# 01-ESP32-ps2-blueretro.net
KiCad netlist of a schematic drawn in Altium Designer
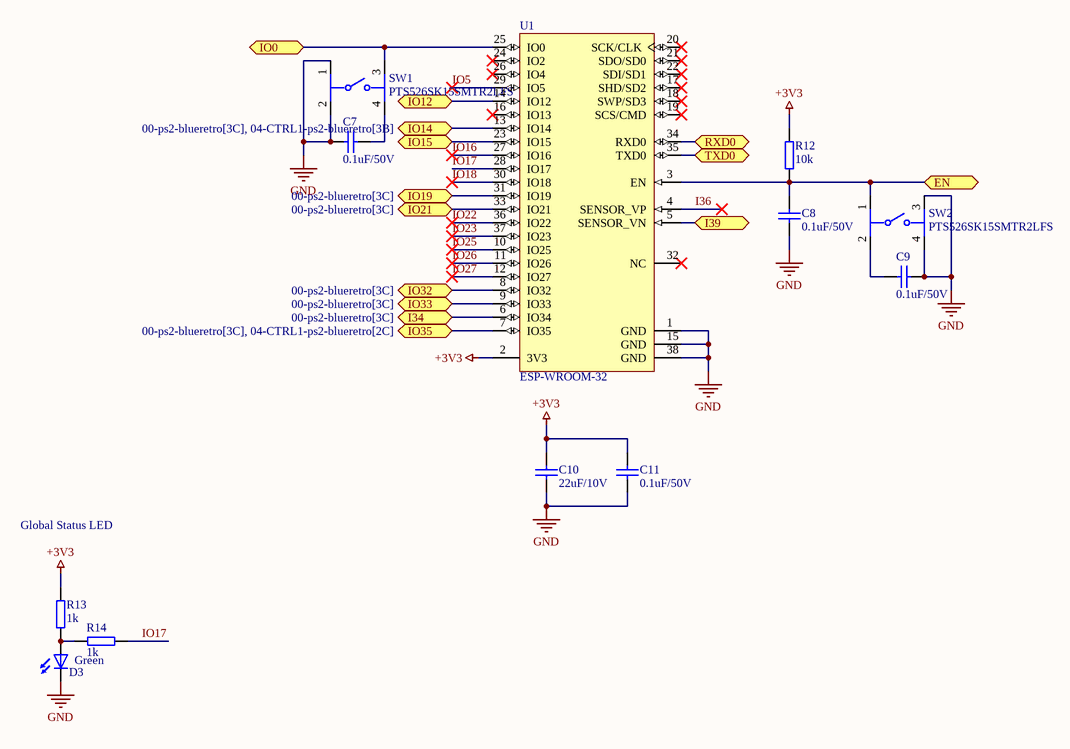
[diagram p0: 01-ESP32-ps2-blueretro.SchDoc]

(export (version "E")
  (design (tool "Eeschema 10.0.6"))
  (components
    (comp (ref "C7")
      (value "0.1uF/50V")
      (footprint "cap_0603")
      (fields (field (name "Comment") "cap_0603"))
      (libsource (lib "mycomponents") (part "cap_0603"))
    )
    (comp (ref "C8")
      (value "0.1uF/50V")
      (footprint "cap_0603")
      (fields (field (name "Comment") "cap_0603"))
      (libsource (lib "mycomponents") (part "cap_0603"))
    )
    (comp (ref "C9")
      (value "0.1uF/50V")
      (footprint "cap_0603")
      (fields (field (name "Comment") "cap_0603"))
      (libsource (lib "mycomponents") (part "cap_0603"))
    )
    (comp (ref "C10")
      (value "22uF/10V")
      (footprint "cap_0603")
      (fields (field (name "Comment") "cap_0603"))
      (libsource (lib "mycomponents") (part "cap_0603"))
    )
    (comp (ref "C11")
      (value "0.1uF/50V")
      (footprint "cap_0603")
      (fields (field (name "Comment") "cap_0603"))
      (libsource (lib "mycomponents") (part "cap_0603"))
    )
    (comp (ref "D3")
      (value "Green")
      (footprint "led0603_GREEN")
      (description "Green 3,2V 20mA")
      (fields
        (field (name "MANUFACTURER") "Würth Elektronik")
        (field (name "MANUFACTURER PART NUMBER") "150060GS75000")
      )
      (libsource (lib "mycomponents") (part "led_0603"))
    )
    (comp (ref "R12")
      (value "10k")
      (footprint "res_0603")
      (fields (field (name "Comment") "res_0603"))
      (libsource (lib "mycomponents") (part "res_0603"))
    )
    (comp (ref "R13")
      (value "1k")
      (footprint "res_0603")
      (fields (field (name "Comment") "res_0603"))
      (libsource (lib "mycomponents") (part "res_0603"))
    )
    (comp (ref "R14")
      (value "1k")
      (footprint "res_0603")
      (fields (field (name "Comment") "res_0603"))
      (libsource (lib "mycomponents") (part "res_0603"))
    )
    (comp (ref "SW1")
      (value "PTS526SK15SMTR2LFS")
      (footprint "FP-PTS526SK15SMTR2LFS-MFG")
      (description "TACT 5.2 X 5.2, 1.5 MM H, 260GF,")
      (fields
        (field (name "MANUFACTURER") "C&K")
        (field (name "OCTOPART") "https://octopart.com/pts526+sk15+smtr2+lfs-c%26k+components-100617999")
      )
      (libsource (lib "Altium Content Vault") (part "b8895f3f4cefb76e1819d2863dba89b"))
    )
    (comp (ref "SW2")
      (value "PTS526SK15SMTR2LFS")
      (footprint "FP-PTS526SK15SMTR2LFS-MFG")
      (description "TACT 5.2 X 5.2, 1.5 MM H, 260GF,")
      (fields
        (field (name "MANUFACTURER") "C&K")
        (field (name "OCTOPART") "https://octopart.com/pts526+sk15+smtr2+lfs-c%26k+components-100617999")
      )
      (libsource (lib "Altium Content Vault") (part "b8895f3f4cefb76e1819d2863dba89b"))
    )
    (comp (ref "U1")
      (value "ESP-WROOM-32")
      (footprint "OLMX-ESP-WROOM-32")
      (description "Espressif System, 2.7 to 3.6 V, -40 to 85 degC, 38-Pin SMD")
      (fields (field (name "MANUFACTURER") "Olimex"))
      (libsource (lib "Altium Content Vault") (part "OLMX-ESP-WROOM-32-38"))
    )
  )
  (nets
    (net (code "1") (name "+3V3") (class "Default")
      (node (ref "C10") (pin "2") (pinfunction "2_2") (pintype "passive"))
      (node (ref "C11") (pin "2") (pinfunction "2_2") (pintype "passive"))
      (node (ref "R12") (pin "1") (pinfunction "1_1") (pintype "passive"))
      (node (ref "R13") (pin "2") (pinfunction "2_2") (pintype "passive"))
      (node (ref "U1") (pin "2") (pinfunction "3V3_2") (pintype "power_in"))
    )
    (net (code "2") (name "/EN") (class "Default")
      (node (ref "C8") (pin "2") (pinfunction "2_2") (pintype "passive"))
      (node (ref "R12") (pin "2") (pinfunction "2_2") (pintype "passive"))
      (node (ref "SW2") (pin "1") (pinfunction "1_1") (pintype "passive"))
      (node (ref "U1") (pin "3") (pinfunction "EN_3") (pintype "input"))
    )
    (net (code "3") (name "/I34") (class "Default")
      (node (ref "U1") (pin "6") (pinfunction "IO34_6") (pintype "bidirectional"))
    )
    (net (code "4") (name "/I36") (class "Default")
      (node (ref "U1") (pin "4") (pinfunction "SENSOR_VP_4") (pintype "input+no_connect"))
    )
    (net (code "5") (name "/I39") (class "Default")
      (node (ref "U1") (pin "5") (pinfunction "SENSOR_VN_5") (pintype "input"))
    )
    (net (code "6") (name "/IO0") (class "Default")
      (node (ref "SW1") (pin "3") (pinfunction "3_3") (pintype "passive"))
      (node (ref "U1") (pin "25") (pinfunction "IO0_25") (pintype "bidirectional"))
    )
    (net (code "7") (name "/IO5") (class "Default")
      (node (ref "U1") (pin "29") (pinfunction "IO5_29") (pintype "bidirectional+no_connect"))
    )
    (net (code "8") (name "/IO12") (class "Default")
      (node (ref "U1") (pin "14") (pinfunction "IO12_14") (pintype "bidirectional"))
    )
    (net (code "9") (name "/IO14") (class "Default")
      (node (ref "U1") (pin "13") (pinfunction "IO14_13") (pintype "bidirectional"))
    )
    (net (code "10") (name "/IO15") (class "Default")
      (node (ref "U1") (pin "23") (pinfunction "IO15_23") (pintype "bidirectional"))
    )
    (net (code "11") (name "/IO16") (class "Default")
      (node (ref "U1") (pin "27") (pinfunction "IO16_27") (pintype "bidirectional+no_connect"))
    )
    (net (code "12") (name "/IO17") (class "Default")
      (node (ref "R14") (pin "1") (pinfunction "1_1") (pintype "passive"))
      (node (ref "U1") (pin "28") (pinfunction "IO17_28") (pintype "bidirectional"))
    )
    (net (code "13") (name "/IO18") (class "Default")
      (node (ref "U1") (pin "30") (pinfunction "IO18_30") (pintype "bidirectional+no_connect"))
    )
    (net (code "14") (name "/IO19") (class "Default")
      (node (ref "U1") (pin "31") (pinfunction "IO19_31") (pintype "bidirectional"))
    )
    (net (code "15") (name "/IO21") (class "Default")
      (node (ref "U1") (pin "33") (pinfunction "IO21_33") (pintype "bidirectional"))
    )
    (net (code "16") (name "/IO22") (class "Default")
      (node (ref "U1") (pin "36") (pinfunction "IO22_36") (pintype "bidirectional+no_connect"))
    )
    (net (code "17") (name "/IO23") (class "Default")
      (node (ref "U1") (pin "37") (pinfunction "IO23_37") (pintype "bidirectional+no_connect"))
    )
    (net (code "18") (name "/IO25") (class "Default")
      (node (ref "U1") (pin "10") (pinfunction "IO25_10") (pintype "bidirectional+no_connect"))
    )
    (net (code "19") (name "/IO26") (class "Default")
      (node (ref "U1") (pin "11") (pinfunction "IO26_11") (pintype "bidirectional+no_connect"))
    )
    (net (code "20") (name "/IO27") (class "Default")
      (node (ref "U1") (pin "12") (pinfunction "IO27_12") (pintype "bidirectional+no_connect"))
    )
    (net (code "21") (name "/IO32") (class "Default")
      (node (ref "U1") (pin "8") (pinfunction "IO32_8") (pintype "bidirectional"))
    )
    (net (code "22") (name "/IO33") (class "Default")
      (node (ref "U1") (pin "9") (pinfunction "IO33_9") (pintype "bidirectional"))
    )
    (net (code "23") (name "/IO35") (class "Default")
      (node (ref "U1") (pin "7") (pinfunction "IO35_7") (pintype "bidirectional"))
    )
    (net (code "24") (name "/RXD0") (class "Default")
      (node (ref "U1") (pin "34") (pinfunction "RXD0_34") (pintype "bidirectional"))
    )
    (net (code "25") (name "/TXD0") (class "Default")
      (node (ref "U1") (pin "35") (pinfunction "TXD0_35") (pintype "bidirectional"))
    )
    (net (code "26") (name "GND") (class "Default")
      (node (ref "C10") (pin "1") (pinfunction "1_1") (pintype "passive"))
      (node (ref "C11") (pin "1") (pinfunction "1_1") (pintype "passive"))
      (node (ref "C7") (pin "2") (pinfunction "2_2") (pintype "passive"))
      (node (ref "C8") (pin "1") (pinfunction "1_1") (pintype "passive"))
      (node (ref "C9") (pin "2") (pinfunction "2_2") (pintype "passive"))
      (node (ref "D3") (pin "2") (pinfunction "C_2") (pintype "passive"))
      (node (ref "SW1") (pin "1") (pinfunction "1_1") (pintype "passive"))
      (node (ref "SW1") (pin "2") (pinfunction "2_2") (pintype "passive"))
      (node (ref "SW2") (pin "3") (pinfunction "3_3") (pintype "passive"))
      (node (ref "SW2") (pin "4") (pinfunction "4_4") (pintype "passive"))
      (node (ref "U1") (pin "1") (pinfunction "GND_1") (pintype "power_in"))
      (node (ref "U1") (pin "15") (pinfunction "GND_15") (pintype "power_in"))
      (node (ref "U1") (pin "38") (pinfunction "GND_38") (pintype "power_in"))
    )
    (net (code "27") (name "Net-(C7-Pad1)") (class "Default")
      (node (ref "C7") (pin "1") (pinfunction "1_1") (pintype "passive"))
      (node (ref "SW1") (pin "4") (pinfunction "4_4") (pintype "passive"))
    )
    (net (code "28") (name "Net-(C9-Pad1)") (class "Default")
      (node (ref "C9") (pin "1") (pinfunction "1_1") (pintype "passive"))
      (node (ref "SW2") (pin "2") (pinfunction "2_2") (pintype "passive"))
    )
    (net (code "29") (name "Net-(D3-A)") (class "Default")
      (node (ref "D3") (pin "1") (pinfunction "A_1") (pintype "passive"))
      (node (ref "R13") (pin "1") (pinfunction "1_1") (pintype "passive"))
      (node (ref "R14") (pin "2") (pinfunction "2_2") (pintype "passive"))
    )
    (net (code "30") (name "unconnected-(U1-IO2-Pad24)") (class "Default")
      (node (ref "U1") (pin "24") (pinfunction "IO2_24") (pintype "bidirectional+no_connect"))
    )
    (net (code "31") (name "unconnected-(U1-IO4-Pad26)") (class "Default")
      (node (ref "U1") (pin "26") (pinfunction "IO4_26") (pintype "bidirectional+no_connect"))
    )
    (net (code "32") (name "unconnected-(U1-IO13-Pad16)") (class "Default")
      (node (ref "U1") (pin "16") (pinfunction "IO13_16") (pintype "bidirectional+no_connect"))
    )
    (net (code "33") (name "unconnected-(U1-NC-Pad32)") (class "Default")
      (node (ref "U1") (pin "32") (pinfunction "NC_32") (pintype "passive+no_connect"))
    )
    (net (code "34") (name "unconnected-(U1-SCK{slash}CLK-Pad20)") (class "Default")
      (node (ref "U1") (pin "20") (pinfunction "SCK/CLK_20") (pintype "bidirectional+no_connect"))
    )
    (net (code "35") (name "unconnected-(U1-SCS{slash}CMD-Pad19)") (class "Default")
      (node (ref "U1") (pin "19") (pinfunction "SCS/CMD_19") (pintype "bidirectional+no_connect"))
    )
    (net (code "36") (name "unconnected-(U1-SDI{slash}SD1-Pad22)") (class "Default")
      (node (ref "U1") (pin "22") (pinfunction "SDI/SD1_22") (pintype "bidirectional+no_connect"))
    )
    (net (code "37") (name "unconnected-(U1-SDO{slash}SD0-Pad21)") (class "Default")
      (node (ref "U1") (pin "21") (pinfunction "SDO/SD0_21") (pintype "bidirectional+no_connect"))
    )
    (net (code "38") (name "unconnected-(U1-SHD{slash}SD2-Pad17)") (class "Default")
      (node (ref "U1") (pin "17") (pinfunction "SHD/SD2_17") (pintype "bidirectional+no_connect"))
    )
    (net (code "39") (name "unconnected-(U1-SWP{slash}SD3-Pad18)") (class "Default")
      (node (ref "U1") (pin "18") (pinfunction "SWP/SD3_18") (pintype "bidirectional+no_connect"))
    )
  )
)
